# lab3.net
KiCad netlist of a schematic drawn in EAGLE
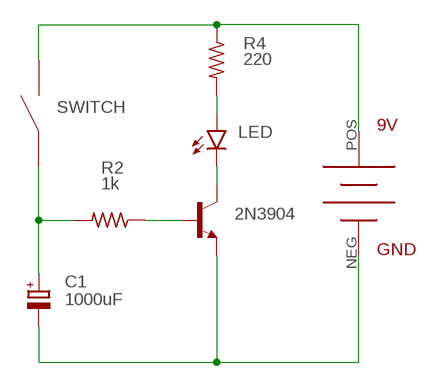
[diagram p0: schematic, sheet 1]

(export (version "E")
  (design (tool "Eeschema 10.0.6"))
  (components
    (comp (ref "C1")
      (value "1000uF")
      (footprint "eagle-import:EB22,5D")
      (libsource (lib "eagle-import") (part "CPOL-EUE10-22.5"))
    )
    (comp (ref "LED")
      (value "LED5MM")
      (footprint "eagle-import:LED5MM")
      (libsource (lib "eagle-import") (part "LED5MM"))
    )
    (comp (ref "R2")
      (value "1k")
      (footprint "eagle-import:0207_10")
      (libsource (lib "eagle-import") (part "R-US_0207/10"))
    )
    (comp (ref "R4")
      (value "220")
      (footprint "eagle-import:0207_10")
      (libsource (lib "eagle-import") (part "R-US_0207/10"))
    )
    (comp (ref "T3")
      (value "2N3904")
      (footprint "eagle-import:TO92")
      (libsource (lib "eagle-import") (part "2N3904"))
    )
    (comp (ref "U$1")
      (value "PWR_DEMO")
      (footprint "eagle-import:PWR_DEMO")
      (libsource (lib "eagle-import") (part "PWR_DEMO"))
    )
    (comp (ref "U$2")
      (value "TACT_SWITCH_6MM")
      (footprint "eagle-import:TACT_SWITCH_6MM")
      (libsource (lib "eagle-import") (part "TACT_SWITCH_6MM"))
    )
  )
  (nets
    (net (code "1") (name "Net-(C1-Pad+)") (class "Default")
      (node (ref "C1") (pin "+") (pinfunction "+_+") (pintype "passive"))
      (node (ref "R2") (pin "2") (pinfunction "2_2") (pintype "passive"))
      (node (ref "U$2") (pin "A1") (pinfunction "A_A1") (pintype "bidirectional"))
      (node (ref "U$2") (pin "A2") (pinfunction "A_A2") (pintype "bidirectional"))
    )
    (net (code "2") (name "Net-(LED-C)") (class "Default")
      (node (ref "LED") (pin "K") (pinfunction "C_K") (pintype "passive"))
      (node (ref "T3") (pin "1") (pinfunction "C_1") (pintype "passive"))
    )
    (net (code "3") (name "Net-(LED-PadA)") (class "Default")
      (node (ref "LED") (pin "A") (pinfunction "A_A") (pintype "passive"))
      (node (ref "R4") (pin "2") (pinfunction "2_2") (pintype "passive"))
    )
    (net (code "4") (name "Net-(R4-Pad1)") (class "Default")
      (node (ref "R4") (pin "1") (pinfunction "1_1") (pintype "passive"))
      (node (ref "U$1") (pin "POS") (pinfunction "POS_POS") (pintype "bidirectional"))
      (node (ref "U$2") (pin "B1") (pinfunction "B_B1") (pintype "bidirectional"))
      (node (ref "U$2") (pin "B2") (pinfunction "B_B2") (pintype "bidirectional"))
    )
    (net (code "5") (name "Net-(T3-B)") (class "Default")
      (node (ref "R2") (pin "1") (pinfunction "1_1") (pintype "passive"))
      (node (ref "T3") (pin "2") (pinfunction "B_2") (pintype "passive"))
    )
    (net (code "6") (name "Net-(T3-E)") (class "Default")
      (node (ref "C1") (pin "-") (pinfunction "-_-") (pintype "passive"))
      (node (ref "T3") (pin "3") (pinfunction "E_3") (pintype "passive"))
      (node (ref "U$1") (pin "NEG") (pinfunction "NEG_NEG") (pintype "bidirectional"))
    )
  )
)
